# JBC_PD_Front_End.net
KiCad netlist of a schematic drawn in Altium Designer
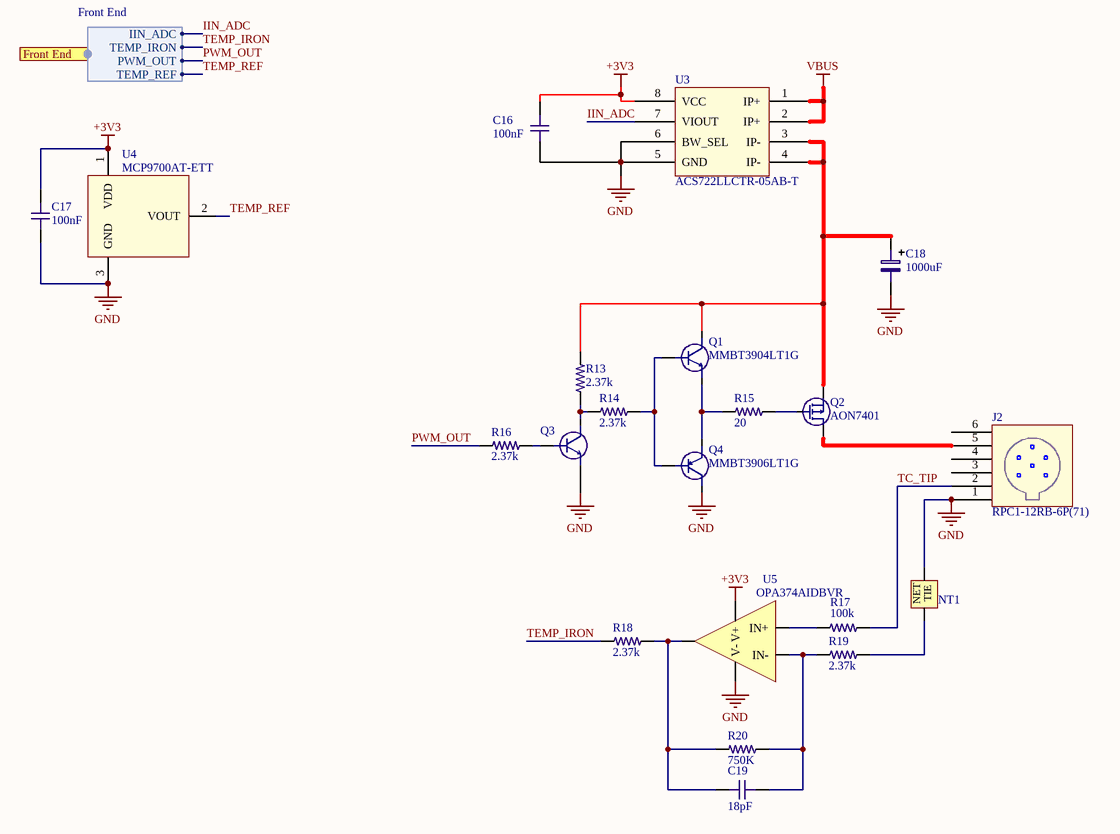
[diagram p0: JBC_PD_Front_End.SchDoc]

(export (version "E")
  (design (tool "Eeschema 10.0.6"))
  (components
    (comp (ref "C16")
      (value "100nF")
      (footprint "C0603-IPC")
      (description "Chip Capacitor, 0603, 100nF, 25V, X7R")
      (fields (field (name "Comment") "C0603 100nF 25V X7R"))
      (libsource (lib "Capacitors") (part "C0603 100nF 25V X7R"))
    )
    (comp (ref "C17")
      (value "100nF")
      (footprint "C0603-IPC")
      (description "Chip Capacitor, 0603, 100nF, 25V, X7R")
      (fields (field (name "Comment") "C0603 100nF 25V X7R"))
      (libsource (lib "Capacitors") (part "C0603 100nF 25V X7R"))
    )
    (comp (ref "C18")
      (value "1000uF")
      (footprint "C-POLARIZED-5-12.5 Horizontal")
      (fields (field (name "Comment") "35ZLH1000MEFC12.5X20"))
      (libsource (lib "Capacitors") (part "C-THT 1000uF 35V Electrolytic"))
    )
    (comp (ref "C19")
      (value "18pF")
      (footprint "C0402-IPC")
      (description "Chip Capacitor, 0402, 18pF, 25V, C0G")
      (fields (field (name "Comment") "C0402 18pF 50V C0G_1"))
      (libsource (lib "Capacitors") (part "C0402 18pF 50V C0G_1"))
    )
    (comp (ref "J2")
      (value "RPC1-12RB-6P(71)")
      (footprint "HIROSE RPC 1 SMD (WIRE)")
      (description "6 Position Circular Connector Receptacle, Male Pins Solder Cup (JBC Iron Conn)")
      (libsource (lib "Connectors") (part "Hirose RPC1"))
    )
    (comp (ref "NT1")
      (value "Net Tie")
      (footprint "NET_TIE")
      (libsource (lib "Virtual Parts") (part "Net Tie"))
    )
    (comp (ref "Q1")
      (value "MMBT3904LT1G")
      (footprint "SOT23-MMBT3904")
      (description "Bipolar (BJT) Transistor NPN 40V 200mA 300MHz 300mW Surface Mount SOT-23-3 (TO-236)")
      (libsource (lib "Transistors") (part "MMBT3904LT1G"))
    )
    (comp (ref "Q2")
      (value "AON7401")
      (footprint "DFN3x3A_8L_EP1_P")
      (description "P-Channel 30V 12A (Ta), 35A (Tc) 3.1W (Ta), 29W (Tc) Surface Mount 8-DFN (3x3)")
      (libsource (lib "Transistors") (part "AON7401"))
    )
    (comp (ref "Q3")
      (value "MMBT3904LT1G")
      (footprint "SOT23-MMBT3904")
      (description "Bipolar (BJT) Transistor NPN 40V 200mA 300MHz 300mW Surface Mount SOT-23-3 (TO-236)")
      (libsource (lib "Transistors") (part "MMBT3904LT1G"))
    )
    (comp (ref "Q4")
      (value "MMBT3906LT1G")
      (footprint "SOT23-Generic")
      (description "Bipolar (BJT) Transistor PNP 40V 200mA 250MHz 300mW Surface Mount SOT-23-3 (TO-236)")
      (libsource (lib "Transistors") (part "MMBT3906LT1G"))
    )
    (comp (ref "R13")
      (value "2.37k")
      (footprint "R0603-IPC")
      (description "RES SMD 2.37K OHM 1% 1/10W 0603")
      (fields (field (name "Comment") "R0603 2.37K 1%"))
      (libsource (lib "Resistors") (part "R0603 2.37K 1%"))
    )
    (comp (ref "R14")
      (value "2.37k")
      (footprint "R0603-IPC")
      (description "RES SMD 2.37K OHM 1% 1/10W 0603")
      (fields (field (name "Comment") "R0603 2.37K 1%"))
      (libsource (lib "Resistors") (part "R0603 2.37K 1%"))
    )
    (comp (ref "R15")
      (value "20")
      (footprint "R1206-IPC")
      (description "Chip Resistor, 1206, 20 ohms, 0.5W")
      (fields
        (field (name "MANUFACTURER") "Stackpole Electronics Inc.")
        (field (name "MANUFACTURER PART NUMBER") "RNCP1206FTD20R0")
      )
      (libsource (lib "Resistors") (part "R1206 20 1%"))
    )
    (comp (ref "R16")
      (value "2.37k")
      (footprint "R0603-IPC")
      (description "RES SMD 2.37K OHM 1% 1/10W 0603")
      (fields (field (name "Comment") "R0603 2.37K 1%"))
      (libsource (lib "Resistors") (part "R0603 2.37K 1%"))
    )
    (comp (ref "R17")
      (value "100k")
      (footprint "R0603-IPC")
      (description "RES SMD 100K OHM 1% 1/10W 0603")
      (fields (field (name "Comment") "R0603 100K 1%"))
      (libsource (lib "Resistors") (part "R0603 100K 1%"))
    )
    (comp (ref "R18")
      (value "2.37k")
      (footprint "R0603-IPC")
      (description "RES SMD 2.37K OHM 1% 1/10W 0603")
      (fields (field (name "Comment") "R0603 2.37K 1%"))
      (libsource (lib "Resistors") (part "R0603 2.37K 1%"))
    )
    (comp (ref "R19")
      (value "2.37k")
      (footprint "R0603-IPC")
      (description "RES SMD 2.37K OHM 1% 1/10W 0603")
      (fields (field (name "Comment") "R0603 2.37K 1%"))
      (libsource (lib "Resistors") (part "R0603 2.37K 1%"))
    )
    (comp (ref "R20")
      (value "750K")
      (footprint "R0603-IPC")
      (description "RES SMD 750K OHM 1% 1/10W 0603")
      (fields (field (name "TOLERANCE") "±1%") (field (name "Comment") "RC0603FR-07750KL"))
      (libsource (lib "Resistors") (part "R0603 750K 1%"))
    )
    (comp (ref "U3")
      (value "ACS722LLCTR-05AB-T")
      (footprint "SOIC127P600X175-8N")
      (description "Current Sensor 5A 1 Channel Hall Effect, Open Loop Bidirectional 8-SOIC (0.154\", 3.90mm Width)")
      (libsource (lib "Integrated Circuits") (part "ACS722"))
    )
    (comp (ref "U4")
      (value "MCP9700AT-ETT")
      (footprint "SOT23")
      (description "Temperature Sensor Analog, Local -40°C ~ 125°C 10mV/°C SOT-23-3")
      (libsource (lib "Integrated Circuits") (part "MCP9700AT-ETT"))
    )
    (comp (ref "U5")
      (value "OPA374AIDBVR")
      (footprint "DBV0005A")
      (description "General Purpose 1 2.3V ~ 5.5V, ±1.15V ~ 2.75V 585uA 6.5MHz 5 V/us SOT-23-5 Precision OpAmps RoHS")
      (libsource (lib "Integrated Circuits") (part "OPA374"))
    )
  )
  (nets
    (net (code "3") (name "+3V3") (class "Default")
      (node (ref "C16") (pin "2") (pintype "passive"))
      (node (ref "C17") (pin "2") (pintype "passive"))
      (node (ref "U3") (pin "8") (pinfunction "VCC_8") (pintype "passive"))
      (node (ref "U4") (pin "1") (pinfunction "VDD_1") (pintype "passive"))
      (node (ref "U5") (pin "5") (pinfunction "V+_5") (pintype "passive"))
    )
    (net (code "4") (name "/IIN_ADC") (class "Default")
      (node (ref "U3") (pin "7") (pinfunction "VIOUT_7") (pintype "passive"))
    )
    (net (code "5") (name "/PWM_OUT") (class "Default") (node (ref "R16") (pin "1") (pintype "passive")))
    (net (code "6") (name "/TC_TIP") (class "Default")
      (node (ref "J2") (pin "2") (pinfunction "2_2") (pintype "passive"))
      (node (ref "R17") (pin "1") (pintype "passive"))
    )
    (net (code "7") (name "/TEMP_IRON") (class "Default") (node (ref "R18") (pin "1") (pintype "passive")))
    (net (code "8") (name "/TEMP_REF") (class "Default")
      (node (ref "U4") (pin "2") (pinfunction "VOUT_2") (pintype "passive"))
    )
    (net (code "10") (name "GND") (class "Default")
      (node (ref "C16") (pin "1") (pintype "passive"))
      (node (ref "C17") (pin "1") (pintype "passive"))
      (node (ref "C18") (pin "2") (pintype "passive"))
      (node (ref "J2") (pin "1") (pinfunction "1_1") (pintype "passive"))
      (node (ref "NT1") (pin "2") (pinfunction "2_2") (pintype "passive"))
      (node (ref "Q3") (pin "2") (pinfunction "E_2") (pintype "passive"))
      (node (ref "Q4") (pin "3") (pinfunction "C_3") (pintype "passive"))
      (node (ref "U3") (pin "5") (pinfunction "GND_5") (pintype "passive"))
      (node (ref "U3") (pin "6") (pinfunction "BW_SEL_6") (pintype "passive"))
      (node (ref "U4") (pin "3") (pinfunction "GND_3") (pintype "passive"))
      (node (ref "U5") (pin "2") (pinfunction "V-_2") (pintype "passive"))
    )
    (net (code "11") (name "Net-(J2-Pad5)") (class "Default")
      (node (ref "J2") (pin "5") (pinfunction "5_5") (pintype "passive"))
      (node (ref "Q2") (pin "D") (pinfunction "D_D") (pintype "passive"))
    )
    (net (code "12") (name "Net-(NT1-Pad1)") (class "Default")
      (node (ref "NT1") (pin "1") (pinfunction "1_1") (pintype "passive"))
      (node (ref "R19") (pin "2") (pintype "passive"))
    )
    (net (code "13") (name "Net-(Q1-B)") (class "Default")
      (node (ref "Q1") (pin "1") (pinfunction "B_1") (pintype "passive"))
      (node (ref "Q4") (pin "1") (pinfunction "B_1") (pintype "passive"))
      (node (ref "R14") (pin "2") (pintype "passive"))
    )
    (net (code "14") (name "Net-(Q1-C)") (class "Default")
      (node (ref "C18") (pin "1") (pintype "passive"))
      (node (ref "Q1") (pin "3") (pinfunction "C_3") (pintype "passive"))
      (node (ref "Q2") (pin "S") (pinfunction "S_S") (pintype "passive"))
      (node (ref "R13") (pin "2") (pintype "passive"))
      (node (ref "U3") (pin "3") (pinfunction "IP-_3") (pintype "passive"))
      (node (ref "U3") (pin "4") (pinfunction "IP-_4") (pintype "passive"))
    )
    (net (code "15") (name "Net-(Q1-E)") (class "Default")
      (node (ref "Q1") (pin "2") (pinfunction "E_2") (pintype "passive"))
      (node (ref "Q4") (pin "2") (pinfunction "E_2") (pintype "passive"))
      (node (ref "R15") (pin "1") (pintype "passive"))
    )
    (net (code "16") (name "Net-(Q2-PadG)") (class "Default")
      (node (ref "Q2") (pin "G") (pinfunction "G_G") (pintype "passive"))
      (node (ref "R15") (pin "2") (pintype "passive"))
    )
    (net (code "17") (name "Net-(Q3-B)") (class "Default")
      (node (ref "Q3") (pin "1") (pinfunction "B_1") (pintype "passive"))
      (node (ref "R16") (pin "2") (pintype "passive"))
    )
    (net (code "18") (name "Net-(Q3-C)") (class "Default")
      (node (ref "Q3") (pin "3") (pinfunction "C_3") (pintype "passive"))
      (node (ref "R13") (pin "1") (pintype "passive"))
      (node (ref "R14") (pin "1") (pintype "passive"))
    )
    (net (code "19") (name "Net-(U5-IN+)") (class "Default")
      (node (ref "R17") (pin "2") (pintype "passive"))
      (node (ref "U5") (pin "3") (pinfunction "IN+_3") (pintype "passive"))
    )
    (net (code "20") (name "Net-(U5-IN-)") (class "Default")
      (node (ref "C19") (pin "2") (pintype "passive"))
      (node (ref "R19") (pin "1") (pintype "passive"))
      (node (ref "R20") (pin "2") (pintype "passive"))
      (node (ref "U5") (pin "4") (pinfunction "IN-_4") (pintype "passive"))
    )
    (net (code "21") (name "Net-(U5-VOUT)") (class "Default")
      (node (ref "C19") (pin "1") (pintype "passive"))
      (node (ref "R18") (pin "2") (pintype "passive"))
      (node (ref "R20") (pin "1") (pintype "passive"))
      (node (ref "U5") (pin "1") (pinfunction "VOUT_1") (pintype "passive"))
    )
    (net (code "22") (name "VBUS") (class "Default")
      (node (ref "U3") (pin "1") (pinfunction "IP+_1") (pintype "passive"))
      (node (ref "U3") (pin "2") (pinfunction "IP+_2") (pintype "passive"))
    )
    (net (code "23") (name "unconnected-(J2-Pad3)") (class "Default")
      (node (ref "J2") (pin "3") (pinfunction "3_3") (pintype "passive"))
    )
    (net (code "24") (name "unconnected-(J2-Pad4)") (class "Default")
      (node (ref "J2") (pin "4") (pinfunction "4_4") (pintype "passive"))
    )
    (net (code "25") (name "unconnected-(J2-Pad6)") (class "Default")
      (node (ref "J2") (pin "6") (pinfunction "6_6") (pintype "passive"))
    )
  )
)
